# 10MHz_reference_sch.net
KiCad netlist of a schematic drawn in EasyEDA
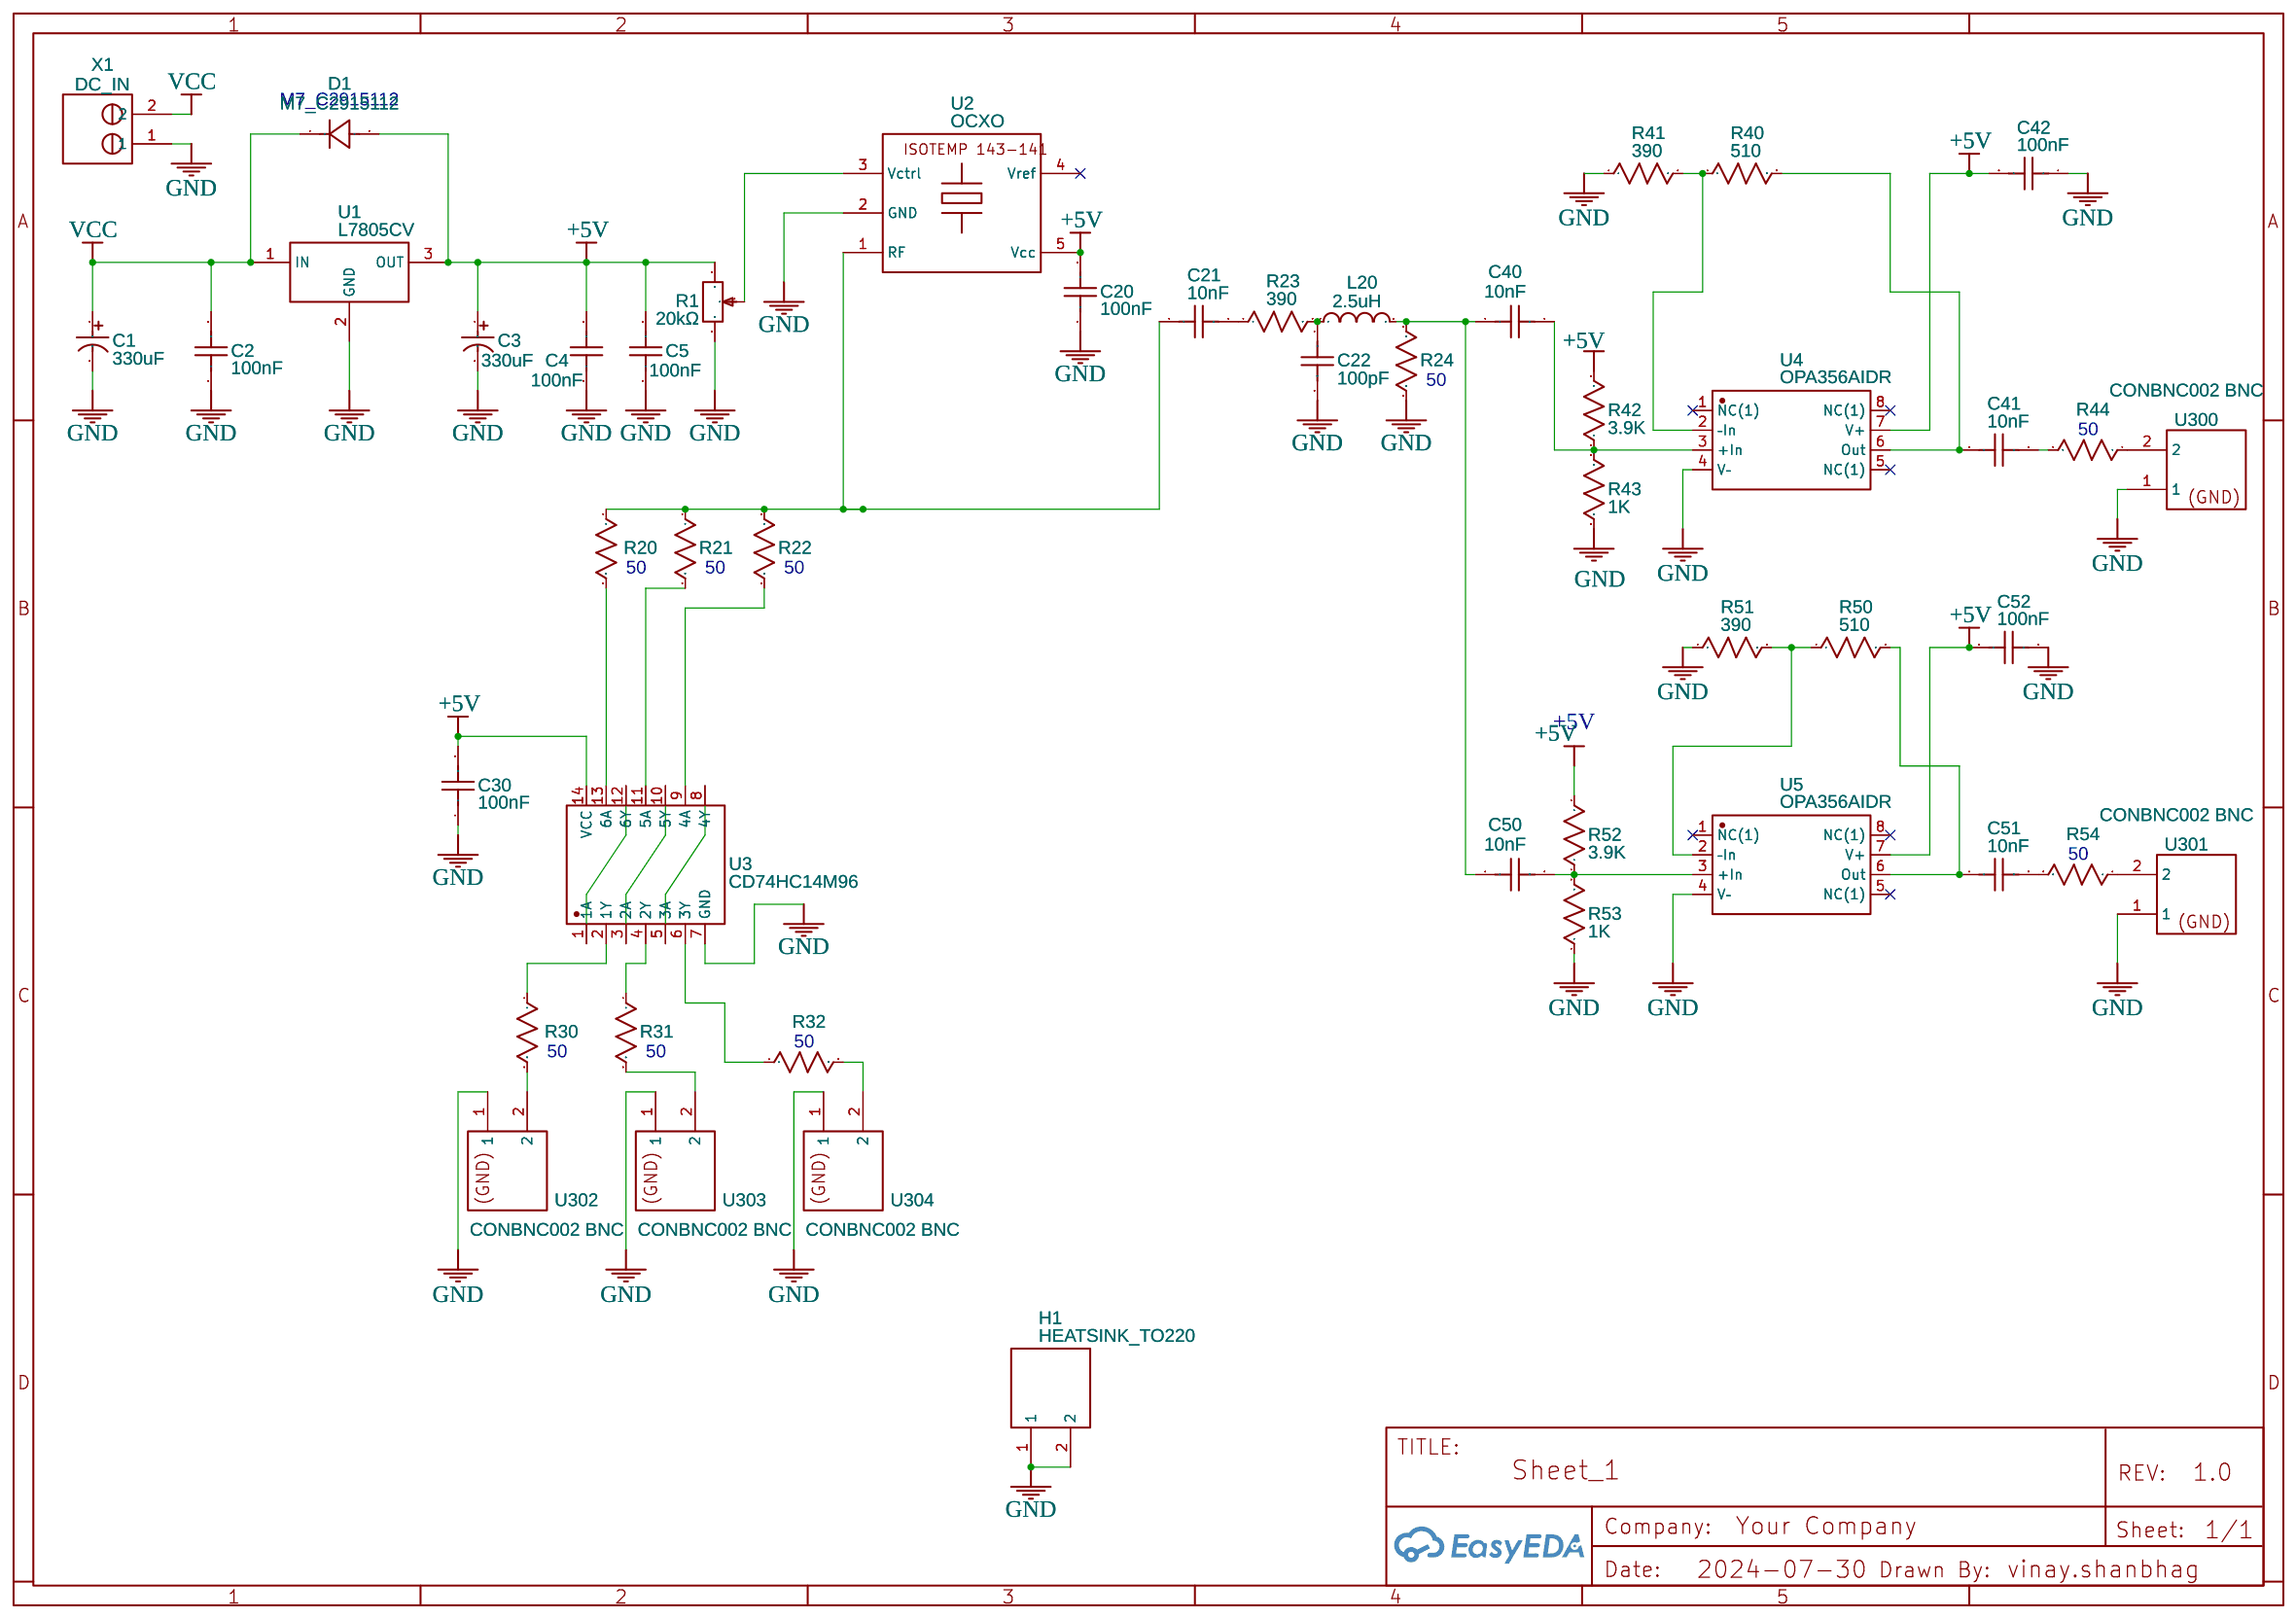
[diagram p0: schematic sheet]

(export (version "E")
  (design (tool "Eeschema 10.0.6"))
  (components
    (comp (ref "C1")
      (value "330uF")
      (fields
        (field (name "Manufacturer Part") "GR337M035F16RR0VL4FP0")
        (field (name "Manufacturer") "CX(承兴)")
      )
      (libsource (lib "") (part "330uF 35V 8*16Green high frequency"))
    )
    (comp (ref "C2")
      (value "100nF")
      (fields
        (field (name "Manufacturer Part") "CC1206KRX7R9BB104")
        (field (name "Manufacturer") "YAGEO(国巨)")
      )
      (libsource (lib "") (part "CC1206KRX7R9BB104"))
    )
    (comp (ref "C3")
      (value "330uF")
      (fields
        (field (name "Manufacturer Part") "GR337M035F16RR0VL4FP0")
        (field (name "Manufacturer") "CX(承兴)")
      )
      (libsource (lib "") (part "330uF 35V 8*16Green high frequency"))
    )
    (comp (ref "C4")
      (value "100nF")
      (fields
        (field (name "Manufacturer Part") "CC1206KRX7R9BB104")
        (field (name "Manufacturer") "YAGEO(国巨)")
      )
      (libsource (lib "") (part "CC1206KRX7R9BB104"))
    )
    (comp (ref "C5")
      (value "100nF")
      (fields
        (field (name "Manufacturer Part") "CC1206KRX7R9BB104")
        (field (name "Manufacturer") "YAGEO(国巨)")
      )
      (libsource (lib "") (part "CC1206KRX7R9BB104"))
    )
    (comp (ref "C20")
      (value "100nF")
      (fields
        (field (name "Manufacturer Part") "CC1206KRX7R9BB104")
        (field (name "Manufacturer") "YAGEO(国巨)")
      )
      (libsource (lib "") (part "CC1206KRX7R9BB104"))
    )
    (comp (ref "C21") (value "10nF") (libsource (lib "") (part "C_0603_US")))
    (comp (ref "C22") (value "100pF") (libsource (lib "") (part "C_0603_US_1")))
    (comp (ref "C30")
      (value "100nF")
      (fields
        (field (name "Manufacturer Part") "CC1206KRX7R9BB104")
        (field (name "Manufacturer") "YAGEO(国巨)")
      )
      (libsource (lib "") (part "CC1206KRX7R9BB104"))
    )
    (comp (ref "C40") (value "10nF") (libsource (lib "") (part "C_0603_US")))
    (comp (ref "C41") (value "10nF") (libsource (lib "") (part "C_0603_US")))
    (comp (ref "C42")
      (value "100nF")
      (fields
        (field (name "Manufacturer Part") "CC1206KRX7R9BB104")
        (field (name "Manufacturer") "YAGEO(国巨)")
      )
      (libsource (lib "") (part "CC1206KRX7R9BB104_1"))
    )
    (comp (ref "C50") (value "10nF") (libsource (lib "") (part "C_0603_US")))
    (comp (ref "C51") (value "10nF") (libsource (lib "") (part "C_0603_US")))
    (comp (ref "C52")
      (value "100nF")
      (fields
        (field (name "Manufacturer Part") "CC1206KRX7R9BB104")
        (field (name "Manufacturer") "YAGEO(国巨)")
      )
      (libsource (lib "") (part "CC1206KRX7R9BB104_1"))
    )
    (comp (ref "D1")
      (value "M7_C2915112")
      (fields (field (name "Manufacturer Part") "M7") (field (name "Manufacturer") "GOODWORK(固得沃克)"))
      (libsource (lib "") (part "M7_C2915112"))
    )
    (comp (ref "H1")
      (value "HEATSINK_TO220")
      (fields (field (name "Manufacturer Part") "HEATSINK TO220"))
      (libsource (lib "") (part "HEATSINK_TO220"))
    )
    (comp (ref "L20") (value "2.5uH") (libsource (lib "") (part "L0603_US")))
    (comp (ref "R1")
      (value "20kΩ")
      (fields (field (name "Manufacturer Part") "3296X-1-203LF") (field (name "Manufacturer") "BOURNS"))
      (libsource (lib "") (part "3296X-1-203LF"))
    )
    (comp (ref "R20") (value "100") (libsource (lib "") (part "R_0603_US")))
    (comp (ref "R21") (value "100") (libsource (lib "") (part "R_0603_US")))
    (comp (ref "R22") (value "100") (libsource (lib "") (part "R_0603_US")))
    (comp (ref "R23") (value "390") (libsource (lib "") (part "R_0603_US_3")))
    (comp (ref "R24") (value "100") (libsource (lib "") (part "R_0603_US")))
    (comp (ref "R30") (value "100") (libsource (lib "") (part "R_0603_US")))
    (comp (ref "R31") (value "100") (libsource (lib "") (part "R_0603_US")))
    (comp (ref "R32") (value "100") (libsource (lib "") (part "R_0603_US_3")))
    (comp (ref "R40") (value "510") (libsource (lib "") (part "R_0603_US_3")))
    (comp (ref "R41") (value "390") (libsource (lib "") (part "R_0603_US_3")))
    (comp (ref "R42") (value "3.9K") (libsource (lib "") (part "R_0603_US_2")))
    (comp (ref "R43") (value "1K") (libsource (lib "") (part "R_0603_US_2")))
    (comp (ref "R44") (value "50") (libsource (lib "") (part "R_0603_US_1")))
    (comp (ref "R50") (value "510") (libsource (lib "") (part "R_0603_US_3")))
    (comp (ref "R51") (value "390") (libsource (lib "") (part "R_0603_US_3")))
    (comp (ref "R52") (value "3.9K") (libsource (lib "") (part "R_0603_US_2")))
    (comp (ref "R53") (value "1K") (libsource (lib "") (part "R_0603_US_2")))
    (comp (ref "R54") (value "50") (libsource (lib "") (part "R_0603_US_1")))
    (comp (ref "U1")
      (value "L7805CV")
      (fields (field (name "Manufacturer") "ST(意法半导体)"))
      (libsource (lib "") (part "L7805CV"))
    )
    (comp (ref "U2")
      (value "OCXO")
      (fields (field (name "Manufacturer Part") "OSC5A2B02 10Mhz") (field (name "Manufacturer") "CTI"))
      (libsource (lib "") (part "OCXO"))
    )
    (comp (ref "U3")
      (value "CD74HC14M96")
      (fields (field (name "Manufacturer") "TI(德州仪器)"))
      (libsource (lib "") (part "CD74HC14M96"))
    )
    (comp (ref "U4")
      (value "OPA356AIDR")
      (fields (field (name "Manufacturer") "TI(德州仪器)"))
      (libsource (lib "") (part "OPA356AIDR"))
    )
    (comp (ref "U5")
      (value "OPA356AIDR")
      (fields (field (name "Manufacturer") "TI(德州仪器)"))
      (libsource (lib "") (part "OPA356AIDR"))
    )
    (comp (ref "U300") (value "CONBNC002 BNC") (libsource (lib "") (part "CONBNC002 BNC")))
    (comp (ref "U301") (value "CONBNC002 BNC") (libsource (lib "") (part "CONBNC002 BNC")))
    (comp (ref "U302") (value "CONBNC002 BNC") (libsource (lib "") (part "CONBNC002 BNC_1")))
    (comp (ref "U303") (value "CONBNC002 BNC") (libsource (lib "") (part "CONBNC002 BNC_1")))
    (comp (ref "U304") (value "CONBNC002 BNC") (libsource (lib "") (part "CONBNC002 BNC_1")))
    (comp (ref "X1") (value "DC_IN") (libsource (lib "") (part "2PScrewTerminalBlock")))
  )
  (nets
    (net (code "1") (name "+5V") (class "Default")
      (node (ref "C20") (pin "2") (pinfunction "2_2") (pintype "unspecified"))
      (node (ref "C3") (pin "1") (pinfunction "1_1") (pintype "input"))
      (node (ref "C30") (pin "2") (pinfunction "2_2") (pintype "unspecified"))
      (node (ref "C4") (pin "2") (pinfunction "2_2") (pintype "unspecified"))
      (node (ref "C42") (pin "2") (pinfunction "2_2") (pintype "unspecified"))
      (node (ref "C5") (pin "2") (pinfunction "2_2") (pintype "unspecified"))
      (node (ref "C52") (pin "2") (pinfunction "2_2") (pintype "unspecified"))
      (node (ref "D1") (pin "2") (pinfunction "A_2") (pintype "unspecified"))
      (node (ref "R1") (pin "1") (pinfunction "1_1") (pintype "input"))
      (node (ref "R42") (pin "2") (pinfunction "2_2") (pintype "unspecified"))
      (node (ref "R52") (pin "2") (pinfunction "2_2") (pintype "unspecified"))
      (node (ref "U1") (pin "3") (pinfunction "OUT_3") (pintype "passive"))
      (node (ref "U2") (pin "5") (pinfunction "Vcc_5") (pintype "unspecified"))
      (node (ref "U3") (pin "14") (pinfunction "VCC_14") (pintype "unspecified"))
      (node (ref "U4") (pin "7") (pinfunction "V+_7") (pintype "unspecified"))
      (node (ref "U5") (pin "7") (pinfunction "V+_7") (pintype "unspecified"))
    )
    (net (code "2") (name "GND") (class "Default")
      (node (ref "C1") (pin "2") (pinfunction "2_2") (pintype "input"))
      (node (ref "C2") (pin "1") (pinfunction "1_1") (pintype "unspecified"))
      (node (ref "C20") (pin "1") (pinfunction "1_1") (pintype "unspecified"))
      (node (ref "C22") (pin "2") (pinfunction "2_2") (pintype "unspecified"))
      (node (ref "C3") (pin "2") (pinfunction "2_2") (pintype "input"))
      (node (ref "C30") (pin "1") (pinfunction "1_1") (pintype "unspecified"))
      (node (ref "C4") (pin "1") (pinfunction "1_1") (pintype "unspecified"))
      (node (ref "C42") (pin "1") (pinfunction "1_1") (pintype "unspecified"))
      (node (ref "C5") (pin "1") (pinfunction "1_1") (pintype "unspecified"))
      (node (ref "C52") (pin "1") (pinfunction "1_1") (pintype "unspecified"))
      (node (ref "H1") (pin "1") (pinfunction "1_1") (pintype "unspecified"))
      (node (ref "H1") (pin "2") (pinfunction "2_2") (pintype "unspecified"))
      (node (ref "R1") (pin "3") (pinfunction "3_3") (pintype "input"))
      (node (ref "R24") (pin "2") (pinfunction "2_2") (pintype "unspecified"))
      (node (ref "R41") (pin "1") (pinfunction "1_1") (pintype "unspecified"))
      (node (ref "R43") (pin "1") (pinfunction "1_1") (pintype "unspecified"))
      (node (ref "R51") (pin "1") (pinfunction "1_1") (pintype "unspecified"))
      (node (ref "R53") (pin "1") (pinfunction "1_1") (pintype "unspecified"))
      (node (ref "U1") (pin "2") (pinfunction "GND_2") (pintype "passive"))
      (node (ref "U2") (pin "2") (pinfunction "GND_2") (pintype "unspecified"))
      (node (ref "U3") (pin "7") (pinfunction "GND_7") (pintype "unspecified"))
      (node (ref "U300") (pin "1") (pinfunction "1_1") (pintype "unspecified"))
      (node (ref "U301") (pin "1") (pinfunction "1_1") (pintype "unspecified"))
      (node (ref "U302") (pin "1") (pinfunction "1_1") (pintype "unspecified"))
      (node (ref "U303") (pin "1") (pinfunction "1_1") (pintype "unspecified"))
      (node (ref "U304") (pin "1") (pinfunction "1_1") (pintype "unspecified"))
      (node (ref "U4") (pin "4") (pinfunction "V–_4") (pintype "unspecified"))
      (node (ref "U5") (pin "4") (pinfunction "V–_4") (pintype "unspecified"))
      (node (ref "X1") (pin "1") (pinfunction "1_1") (pintype "unspecified"))
    )
    (net (code "3") (name "Net-(C21-Pad2)") (class "Default")
      (node (ref "C21") (pin "2") (pinfunction "2_2") (pintype "unspecified"))
      (node (ref "R23") (pin "1") (pinfunction "1_1") (pintype "unspecified"))
    )
    (net (code "4") (name "Net-(C22-Pad1)") (class "Default")
      (node (ref "C22") (pin "1") (pinfunction "1_1") (pintype "unspecified"))
      (node (ref "L20") (pin "1") (pinfunction "1_1") (pintype "unspecified"))
      (node (ref "R23") (pin "2") (pinfunction "2_2") (pintype "unspecified"))
    )
    (net (code "5") (name "Net-(C40-Pad1)") (class "Default")
      (node (ref "C40") (pin "1") (pinfunction "1_1") (pintype "unspecified"))
      (node (ref "C50") (pin "1") (pinfunction "1_1") (pintype "unspecified"))
      (node (ref "L20") (pin "2") (pinfunction "2_2") (pintype "unspecified"))
      (node (ref "R24") (pin "1") (pinfunction "1_1") (pintype "unspecified"))
    )
    (net (code "6") (name "Net-(C41-Pad2)") (class "Default")
      (node (ref "C41") (pin "2") (pinfunction "2_2") (pintype "unspecified"))
      (node (ref "R44") (pin "2") (pinfunction "2_2") (pintype "unspecified"))
    )
    (net (code "7") (name "Net-(C51-Pad2)") (class "Default")
      (node (ref "C51") (pin "2") (pinfunction "2_2") (pintype "unspecified"))
      (node (ref "R54") (pin "2") (pinfunction "2_2") (pintype "unspecified"))
    )
    (net (code "8") (name "Net-(R30-Pad2)") (class "Default")
      (node (ref "R30") (pin "2") (pinfunction "2_2") (pintype "unspecified"))
      (node (ref "U302") (pin "2") (pinfunction "2_2") (pintype "unspecified"))
    )
    (net (code "9") (name "Net-(R31-Pad2)") (class "Default")
      (node (ref "R31") (pin "2") (pinfunction "2_2") (pintype "unspecified"))
      (node (ref "U303") (pin "2") (pinfunction "2_2") (pintype "unspecified"))
    )
    (net (code "10") (name "Net-(R32-Pad2)") (class "Default")
      (node (ref "R32") (pin "2") (pinfunction "2_2") (pintype "unspecified"))
      (node (ref "U304") (pin "2") (pinfunction "2_2") (pintype "unspecified"))
    )
    (net (code "11") (name "Net-(R44-Pad1)") (class "Default")
      (node (ref "R44") (pin "1") (pinfunction "1_1") (pintype "unspecified"))
      (node (ref "U300") (pin "2") (pinfunction "2_2") (pintype "unspecified"))
    )
    (net (code "12") (name "Net-(R54-Pad1)") (class "Default")
      (node (ref "R54") (pin "1") (pinfunction "1_1") (pintype "unspecified"))
      (node (ref "U301") (pin "2") (pinfunction "2_2") (pintype "unspecified"))
    )
    (net (code "13") (name "Net-(U2-RF)") (class "Default")
      (node (ref "C21") (pin "1") (pinfunction "1_1") (pintype "unspecified"))
      (node (ref "R20") (pin "1") (pinfunction "1_1") (pintype "unspecified"))
      (node (ref "R21") (pin "1") (pinfunction "1_1") (pintype "unspecified"))
      (node (ref "R22") (pin "1") (pinfunction "1_1") (pintype "unspecified"))
      (node (ref "U2") (pin "1") (pinfunction "RF_1") (pintype "unspecified"))
    )
    (net (code "14") (name "Net-(U2-Vctrl)") (class "Default")
      (node (ref "R1") (pin "2") (pinfunction "2_2") (pintype "input"))
      (node (ref "U2") (pin "3") (pinfunction "Vctrl_3") (pintype "unspecified"))
    )
    (net (code "15") (name "Net-(U3-1A)") (class "Default")
      (node (ref "U3") (pin "1") (pinfunction "1A_1") (pintype "unspecified"))
      (node (ref "U3") (pin "12") (pinfunction "6Y_12") (pintype "unspecified"))
    )
    (net (code "16") (name "Net-(U3-1Y)") (class "Default")
      (node (ref "R30") (pin "1") (pinfunction "1_1") (pintype "unspecified"))
      (node (ref "U3") (pin "2") (pinfunction "1Y_2") (pintype "unspecified"))
    )
    (net (code "17") (name "Net-(U3-2A)") (class "Default")
      (node (ref "U3") (pin "10") (pinfunction "5Y_10") (pintype "unspecified"))
      (node (ref "U3") (pin "3") (pinfunction "2A_3") (pintype "unspecified"))
    )
    (net (code "18") (name "Net-(U3-2Y)") (class "Default")
      (node (ref "R31") (pin "1") (pinfunction "1_1") (pintype "unspecified"))
      (node (ref "U3") (pin "4") (pinfunction "2Y_4") (pintype "unspecified"))
    )
    (net (code "19") (name "Net-(U3-3A)") (class "Default")
      (node (ref "U3") (pin "5") (pinfunction "3A_5") (pintype "unspecified"))
      (node (ref "U3") (pin "8") (pinfunction "4Y_8") (pintype "unspecified"))
    )
    (net (code "20") (name "Net-(U3-3Y)") (class "Default")
      (node (ref "R32") (pin "1") (pinfunction "1_1") (pintype "unspecified"))
      (node (ref "U3") (pin "6") (pinfunction "3Y_6") (pintype "unspecified"))
    )
    (net (code "21") (name "Net-(U3-4A)") (class "Default")
      (node (ref "R22") (pin "2") (pinfunction "2_2") (pintype "unspecified"))
      (node (ref "U3") (pin "9") (pinfunction "4A_9") (pintype "unspecified"))
    )
    (net (code "22") (name "Net-(U3-5A)") (class "Default")
      (node (ref "R21") (pin "2") (pinfunction "2_2") (pintype "unspecified"))
      (node (ref "U3") (pin "11") (pinfunction "5A_11") (pintype "unspecified"))
    )
    (net (code "23") (name "Net-(U3-6A)") (class "Default")
      (node (ref "R20") (pin "2") (pinfunction "2_2") (pintype "unspecified"))
      (node (ref "U3") (pin "13") (pinfunction "6A_13") (pintype "unspecified"))
    )
    (net (code "24") (name "Net-(U4-+In)") (class "Default")
      (node (ref "C40") (pin "2") (pinfunction "2_2") (pintype "unspecified"))
      (node (ref "R42") (pin "1") (pinfunction "1_1") (pintype "unspecified"))
      (node (ref "R43") (pin "2") (pinfunction "2_2") (pintype "unspecified"))
      (node (ref "U4") (pin "3") (pinfunction "+In_3") (pintype "unspecified"))
    )
    (net (code "25") (name "Net-(U4-Out)") (class "Default")
      (node (ref "C41") (pin "1") (pinfunction "1_1") (pintype "unspecified"))
      (node (ref "R40") (pin "2") (pinfunction "2_2") (pintype "unspecified"))
      (node (ref "U4") (pin "6") (pinfunction "Out_6") (pintype "unspecified"))
    )
    (net (code "26") (name "Net-(U4-–In)") (class "Default")
      (node (ref "R40") (pin "1") (pinfunction "1_1") (pintype "unspecified"))
      (node (ref "R41") (pin "2") (pinfunction "2_2") (pintype "unspecified"))
      (node (ref "U4") (pin "2") (pinfunction "–In_2") (pintype "unspecified"))
    )
    (net (code "27") (name "Net-(U5-+In)") (class "Default")
      (node (ref "C50") (pin "2") (pinfunction "2_2") (pintype "unspecified"))
      (node (ref "R52") (pin "1") (pinfunction "1_1") (pintype "unspecified"))
      (node (ref "R53") (pin "2") (pinfunction "2_2") (pintype "unspecified"))
      (node (ref "U5") (pin "3") (pinfunction "+In_3") (pintype "unspecified"))
    )
    (net (code "28") (name "Net-(U5-Out)") (class "Default")
      (node (ref "C51") (pin "1") (pinfunction "1_1") (pintype "unspecified"))
      (node (ref "R50") (pin "2") (pinfunction "2_2") (pintype "unspecified"))
      (node (ref "U5") (pin "6") (pinfunction "Out_6") (pintype "unspecified"))
    )
    (net (code "29") (name "Net-(U5-–In)") (class "Default")
      (node (ref "R50") (pin "1") (pinfunction "1_1") (pintype "unspecified"))
      (node (ref "R51") (pin "2") (pinfunction "2_2") (pintype "unspecified"))
      (node (ref "U5") (pin "2") (pinfunction "–In_2") (pintype "unspecified"))
    )
    (net (code "30") (name "VCC") (class "Default")
      (node (ref "C1") (pin "1") (pinfunction "1_1") (pintype "input"))
      (node (ref "C2") (pin "2") (pinfunction "2_2") (pintype "unspecified"))
      (node (ref "D1") (pin "1") (pinfunction "K_1") (pintype "unspecified"))
      (node (ref "U1") (pin "1") (pinfunction "IN_1") (pintype "passive"))
      (node (ref "X1") (pin "2") (pinfunction "2_2") (pintype "unspecified"))
    )
    (net (code "31") (name "unconnected-(U2-Vref-Pad4)") (class "Default")
      (node (ref "U2") (pin "4") (pinfunction "Vref_4") (pintype "unspecified+no_connect"))
    )
    (net (code "32") (name "unconnected-(U4-NC(1)-Pad1)") (class "Default")
      (node (ref "U4") (pin "1") (pinfunction "NC(1)_1") (pintype "unspecified+no_connect"))
    )
    (net (code "33") (name "unconnected-(U4-NC(1)-Pad5)") (class "Default")
      (node (ref "U4") (pin "5") (pinfunction "NC(1)_5") (pintype "unspecified+no_connect"))
    )
    (net (code "34") (name "unconnected-(U4-NC(1)-Pad8)") (class "Default")
      (node (ref "U4") (pin "8") (pinfunction "NC(1)_8") (pintype "unspecified+no_connect"))
    )
    (net (code "35") (name "unconnected-(U5-NC(1)-Pad1)") (class "Default")
      (node (ref "U5") (pin "1") (pinfunction "NC(1)_1") (pintype "unspecified+no_connect"))
    )
    (net (code "36") (name "unconnected-(U5-NC(1)-Pad5)") (class "Default")
      (node (ref "U5") (pin "5") (pinfunction "NC(1)_5") (pintype "unspecified+no_connect"))
    )
    (net (code "37") (name "unconnected-(U5-NC(1)-Pad8)") (class "Default")
      (node (ref "U5") (pin "8") (pinfunction "NC(1)_8") (pintype "unspecified+no_connect"))
    )
  )
)
